# power_control.net
KiCad netlist of a schematic drawn in EAGLE
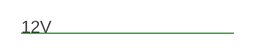
[diagram p0: schematic, sheet 1]
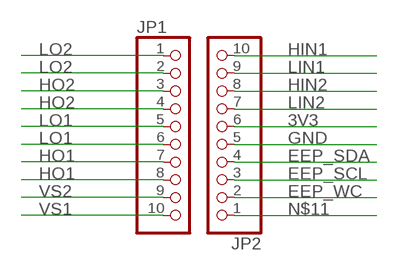
[diagram p1: schematic, sheet 2]
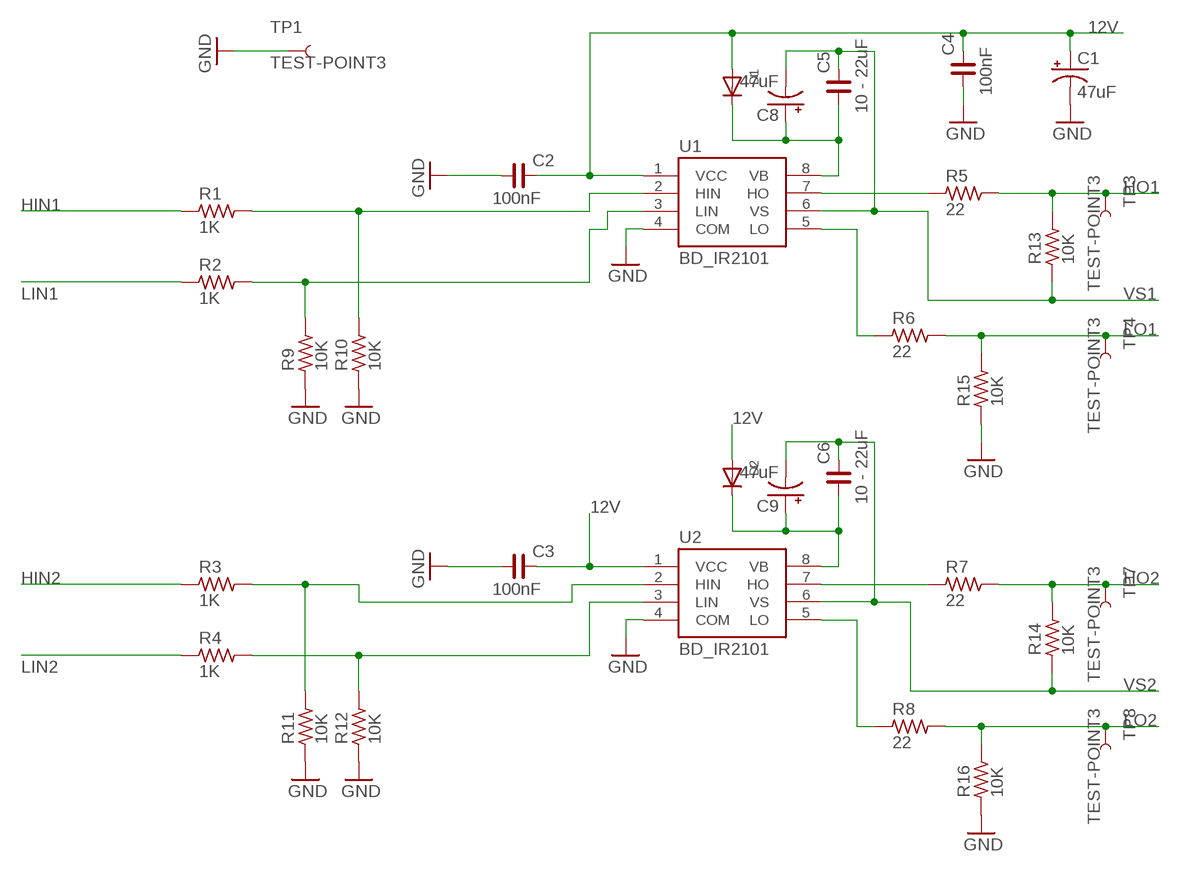
[diagram p2: schematic, sheet 3]
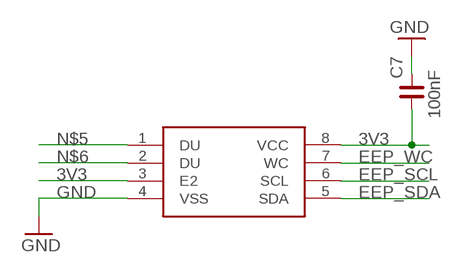
[diagram p3: schematic, sheet 4]

(export (version "E")
  (design (tool "Eeschema 10.0.6"))
  (components
    (comp (ref "JP1")
      (value "PINHD-1X10_2.54-SMD")
      (footprint "eagle-import:1X10SMD")
      (libsource (lib "eagle-import") (part "PINHD-1X10_2.54-SMD"))
    )
    (comp (ref "JP2")
      (value "PINHD-1X10_2.54-SMD")
      (footprint "eagle-import:1X10SMD")
      (libsource (lib "eagle-import") (part "PINHD-1X10_2.54-SMD"))
    )
    (comp (ref "C1")
      (value "47uF")
      (footprint "eagle-import:B_3528-21W")
      (libsource (lib "eagle-import") (part "CPOL-USB/3528-21W"))
    )
    (comp (ref "C2")
      (value "100nF")
      (footprint "eagle-import:C0201")
      (libsource (lib "eagle-import") (part "C_0201"))
    )
    (comp (ref "C3")
      (value "100nF")
      (footprint "eagle-import:C0201")
      (libsource (lib "eagle-import") (part "C_0201"))
    )
    (comp (ref "C4")
      (value "100nF")
      (footprint "eagle-import:C0201")
      (libsource (lib "eagle-import") (part "C_0201"))
    )
    (comp (ref "C5")
      (value "10 - 22uF")
      (footprint "eagle-import:C0805")
      (libsource (lib "eagle-import") (part "C_0805"))
    )
    (comp (ref "C6")
      (value "10 - 22uF")
      (footprint "eagle-import:C0805")
      (libsource (lib "eagle-import") (part "C_0805"))
    )
    (comp (ref "C8")
      (value "47uF")
      (footprint "eagle-import:B_3528-21W")
      (libsource (lib "eagle-import") (part "CPOL-USB/3528-21W"))
    )
    (comp (ref "C9")
      (value "47uF")
      (footprint "eagle-import:B_3528-21W")
      (libsource (lib "eagle-import") (part "CPOL-USB/3528-21W"))
    )
    (comp (ref "D1")
      (value "DIODESOD-523")
      (footprint "eagle-import:SOD-523")
      (libsource (lib "eagle-import") (part "DIODESOD-523"))
    )
    (comp (ref "D2")
      (value "DIODESOD-523")
      (footprint "eagle-import:SOD-523")
      (libsource (lib "eagle-import") (part "DIODESOD-523"))
    )
    (comp (ref "R1")
      (value "1K")
      (footprint "eagle-import:R0201")
      (libsource (lib "eagle-import") (part "R_0201"))
    )
    (comp (ref "R2")
      (value "1K")
      (footprint "eagle-import:R0201")
      (libsource (lib "eagle-import") (part "R_0201"))
    )
    (comp (ref "R3")
      (value "1K")
      (footprint "eagle-import:R0201")
      (libsource (lib "eagle-import") (part "R_0201"))
    )
    (comp (ref "R4")
      (value "1K")
      (footprint "eagle-import:R0201")
      (libsource (lib "eagle-import") (part "R_0201"))
    )
    (comp (ref "R5")
      (value "22")
      (footprint "eagle-import:R0805")
      (libsource (lib "eagle-import") (part "R_0805"))
    )
    (comp (ref "R6")
      (value "22")
      (footprint "eagle-import:R0805")
      (libsource (lib "eagle-import") (part "R_0805"))
    )
    (comp (ref "R7")
      (value "22")
      (footprint "eagle-import:R0805")
      (libsource (lib "eagle-import") (part "R_0805"))
    )
    (comp (ref "R8")
      (value "22")
      (footprint "eagle-import:R0805")
      (libsource (lib "eagle-import") (part "R_0805"))
    )
    (comp (ref "R9")
      (value "10K")
      (footprint "eagle-import:R0201")
      (libsource (lib "eagle-import") (part "R_0201"))
    )
    (comp (ref "R10")
      (value "10K")
      (footprint "eagle-import:R0201")
      (libsource (lib "eagle-import") (part "R_0201"))
    )
    (comp (ref "R11")
      (value "10K")
      (footprint "eagle-import:R0201")
      (libsource (lib "eagle-import") (part "R_0201"))
    )
    (comp (ref "R12")
      (value "10K")
      (footprint "eagle-import:R0201")
      (libsource (lib "eagle-import") (part "R_0201"))
    )
    (comp (ref "R13")
      (value "10K")
      (footprint "eagle-import:R0805")
      (libsource (lib "eagle-import") (part "R_0805"))
    )
    (comp (ref "R14")
      (value "10K")
      (footprint "eagle-import:R0805")
      (libsource (lib "eagle-import") (part "R_0805"))
    )
    (comp (ref "R15")
      (value "10K")
      (footprint "eagle-import:R0805")
      (libsource (lib "eagle-import") (part "R_0805"))
    )
    (comp (ref "R16")
      (value "10K")
      (footprint "eagle-import:R0805")
      (libsource (lib "eagle-import") (part "R_0805"))
    )
    (comp (ref "TP1")
      (value "TEST-POINT3")
      (footprint "eagle-import:PAD.03X.03")
      (libsource (lib "eagle-import") (part "TEST-POINT3"))
    )
    (comp (ref "TP3")
      (value "TEST-POINT3")
      (footprint "eagle-import:PAD.03X.03")
      (libsource (lib "eagle-import") (part "TEST-POINT3"))
    )
    (comp (ref "TP4")
      (value "TEST-POINT3")
      (footprint "eagle-import:PAD.03X.03")
      (libsource (lib "eagle-import") (part "TEST-POINT3"))
    )
    (comp (ref "TP7")
      (value "TEST-POINT3")
      (footprint "eagle-import:PAD.03X.03")
      (libsource (lib "eagle-import") (part "TEST-POINT3"))
    )
    (comp (ref "TP8")
      (value "TEST-POINT3")
      (footprint "eagle-import:PAD.03X.03")
      (libsource (lib "eagle-import") (part "TEST-POINT3"))
    )
    (comp (ref "U1")
      (value "BD_IR2101")
      (footprint "eagle-import:SO8")
      (libsource (lib "eagle-import") (part "BD_IR2101"))
    )
    (comp (ref "U2")
      (value "BD_IR2101")
      (footprint "eagle-import:SO8")
      (libsource (lib "eagle-import") (part "BD_IR2101"))
    )
    (comp (ref "C7")
      (value "100nF")
      (footprint "eagle-import:C0201")
      (libsource (lib "eagle-import") (part "C_0201"))
    )
    (comp (ref "M24M02")
      (value "M24M02-DRMN6TP")
      (footprint "eagle-import:SO08")
      (libsource (lib "eagle-import") (part "M24M02-DRMN6TP"))
    )
  )
  (nets
    (net (code "1") (name "3V3") (class "Default")
      (node (ref "C7") (pin "1") (pinfunction "1_1") (pintype "passive"))
      (node (ref "JP2") (pin "6") (pinfunction "6_6") (pintype "passive"))
      (node (ref "M24M02") (pin "3") (pinfunction "E2_3") (pintype "bidirectional"))
      (node (ref "M24M02") (pin "8") (pinfunction "VCC_8") (pintype "bidirectional"))
    )
    (net (code "2") (name "12V") (class "Default")
      (node (ref "C1") (pin "+") (pinfunction "+_+") (pintype "passive"))
      (node (ref "C2") (pin "2") (pinfunction "2_2") (pintype "passive"))
      (node (ref "C3") (pin "2") (pinfunction "2_2") (pintype "passive"))
      (node (ref "C4") (pin "2") (pinfunction "2_2") (pintype "passive"))
      (node (ref "D1") (pin "A") (pinfunction "A_A") (pintype "passive"))
      (node (ref "D2") (pin "A") (pinfunction "A_A") (pintype "passive"))
      (node (ref "U1") (pin "1") (pinfunction "VCC_1") (pintype "bidirectional"))
      (node (ref "U2") (pin "1") (pinfunction "VCC_1") (pintype "bidirectional"))
    )
    (net (code "3") (name "EEP_SCL") (class "Default")
      (node (ref "JP2") (pin "3") (pinfunction "3_3") (pintype "passive"))
      (node (ref "M24M02") (pin "6") (pinfunction "SCL_6") (pintype "bidirectional"))
    )
    (net (code "4") (name "EEP_SDA") (class "Default")
      (node (ref "JP2") (pin "4") (pinfunction "4_4") (pintype "passive"))
      (node (ref "M24M02") (pin "5") (pinfunction "SDA_5") (pintype "bidirectional"))
    )
    (net (code "5") (name "EEP_WC") (class "Default")
      (node (ref "JP2") (pin "2") (pinfunction "2_2") (pintype "passive"))
      (node (ref "M24M02") (pin "7") (pinfunction "WC_7") (pintype "bidirectional"))
    )
    (net (code "6") (name "GND") (class "Default")
      (node (ref "C1") (pin "-") (pinfunction "-_-") (pintype "passive"))
      (node (ref "C2") (pin "1") (pinfunction "1_1") (pintype "passive"))
      (node (ref "C3") (pin "1") (pinfunction "1_1") (pintype "passive"))
      (node (ref "C4") (pin "1") (pinfunction "1_1") (pintype "passive"))
      (node (ref "C7") (pin "2") (pinfunction "2_2") (pintype "passive"))
      (node (ref "JP2") (pin "5") (pinfunction "5_5") (pintype "passive"))
      (node (ref "M24M02") (pin "4") (pinfunction "VSS_4") (pintype "bidirectional"))
      (node (ref "R10") (pin "1") (pinfunction "1_1") (pintype "passive"))
      (node (ref "R11") (pin "1") (pinfunction "1_1") (pintype "passive"))
      (node (ref "R12") (pin "1") (pinfunction "1_1") (pintype "passive"))
      (node (ref "R15") (pin "1") (pinfunction "1_1") (pintype "passive"))
      (node (ref "R16") (pin "1") (pinfunction "1_1") (pintype "passive"))
      (node (ref "R9") (pin "1") (pinfunction "1_1") (pintype "passive"))
      (node (ref "TP1") (pin "P$1") (pinfunction "1_P$1") (pintype "bidirectional"))
      (node (ref "U1") (pin "4") (pinfunction "COM_4") (pintype "bidirectional"))
      (node (ref "U2") (pin "4") (pinfunction "COM_4") (pintype "bidirectional"))
    )
    (net (code "7") (name "HIN1") (class "Default")
      (node (ref "JP2") (pin "10") (pinfunction "10_10") (pintype "passive"))
      (node (ref "R1") (pin "1") (pinfunction "1_1") (pintype "passive"))
    )
    (net (code "8") (name "HIN2") (class "Default")
      (node (ref "JP2") (pin "8") (pinfunction "8_8") (pintype "passive"))
      (node (ref "R3") (pin "1") (pinfunction "1_1") (pintype "passive"))
    )
    (net (code "9") (name "HO1") (class "Default")
      (node (ref "JP1") (pin "7") (pinfunction "7_7") (pintype "passive"))
      (node (ref "JP1") (pin "8") (pinfunction "8_8") (pintype "passive"))
      (node (ref "R13") (pin "2") (pinfunction "2_2") (pintype "passive"))
      (node (ref "R5") (pin "2") (pinfunction "2_2") (pintype "passive"))
      (node (ref "TP3") (pin "P$1") (pinfunction "1_P$1") (pintype "bidirectional"))
    )
    (net (code "10") (name "HO2") (class "Default")
      (node (ref "JP1") (pin "3") (pinfunction "3_3") (pintype "passive"))
      (node (ref "JP1") (pin "4") (pinfunction "4_4") (pintype "passive"))
      (node (ref "R14") (pin "2") (pinfunction "2_2") (pintype "passive"))
      (node (ref "R7") (pin "2") (pinfunction "2_2") (pintype "passive"))
      (node (ref "TP7") (pin "P$1") (pinfunction "1_P$1") (pintype "bidirectional"))
    )
    (net (code "11") (name "LIN1") (class "Default")
      (node (ref "JP2") (pin "9") (pinfunction "9_9") (pintype "passive"))
      (node (ref "R2") (pin "1") (pinfunction "1_1") (pintype "passive"))
    )
    (net (code "12") (name "LIN2") (class "Default")
      (node (ref "JP2") (pin "7") (pinfunction "7_7") (pintype "passive"))
      (node (ref "R4") (pin "1") (pinfunction "1_1") (pintype "passive"))
    )
    (net (code "13") (name "LO1") (class "Default")
      (node (ref "JP1") (pin "5") (pinfunction "5_5") (pintype "passive"))
      (node (ref "JP1") (pin "6") (pinfunction "6_6") (pintype "passive"))
      (node (ref "R15") (pin "2") (pinfunction "2_2") (pintype "passive"))
      (node (ref "R6") (pin "2") (pinfunction "2_2") (pintype "passive"))
      (node (ref "TP4") (pin "P$1") (pinfunction "1_P$1") (pintype "bidirectional"))
    )
    (net (code "14") (name "LO2") (class "Default")
      (node (ref "JP1") (pin "1") (pinfunction "1_1") (pintype "passive"))
      (node (ref "JP1") (pin "2") (pinfunction "2_2") (pintype "passive"))
      (node (ref "R16") (pin "2") (pinfunction "2_2") (pintype "passive"))
      (node (ref "R8") (pin "2") (pinfunction "2_2") (pintype "passive"))
      (node (ref "TP8") (pin "P$1") (pinfunction "1_P$1") (pintype "bidirectional"))
    )
    (net (code "15") (name "N$5") (class "Default")
      (node (ref "M24M02") (pin "1") (pinfunction "DU_1") (pintype "bidirectional"))
    )
    (net (code "16") (name "N$6") (class "Default")
      (node (ref "M24M02") (pin "2") (pinfunction "DU_2") (pintype "bidirectional"))
    )
    (net (code "17") (name "N$11") (class "Default")
      (node (ref "JP2") (pin "1") (pinfunction "1_1") (pintype "passive"))
    )
    (net (code "18") (name "Net-(D1-C)") (class "Default")
      (node (ref "C5") (pin "1") (pinfunction "1_1") (pintype "passive"))
      (node (ref "C8") (pin "+") (pinfunction "+_+") (pintype "passive"))
      (node (ref "D1") (pin "K") (pinfunction "C_K") (pintype "passive"))
      (node (ref "U1") (pin "8") (pinfunction "VB_8") (pintype "bidirectional"))
    )
    (net (code "19") (name "Net-(D2-C)") (class "Default")
      (node (ref "C6") (pin "1") (pinfunction "1_1") (pintype "passive"))
      (node (ref "C9") (pin "+") (pinfunction "+_+") (pintype "passive"))
      (node (ref "D2") (pin "K") (pinfunction "C_K") (pintype "passive"))
      (node (ref "U2") (pin "8") (pinfunction "VB_8") (pintype "bidirectional"))
    )
    (net (code "20") (name "Net-(U1-HIN)") (class "Default")
      (node (ref "R1") (pin "2") (pinfunction "2_2") (pintype "passive"))
      (node (ref "R10") (pin "2") (pinfunction "2_2") (pintype "passive"))
      (node (ref "U1") (pin "2") (pinfunction "HIN_2") (pintype "bidirectional"))
    )
    (net (code "21") (name "Net-(U1-HO)") (class "Default")
      (node (ref "R5") (pin "1") (pinfunction "1_1") (pintype "passive"))
      (node (ref "U1") (pin "7") (pinfunction "HO_7") (pintype "bidirectional"))
    )
    (net (code "22") (name "Net-(U1-LIN)") (class "Default")
      (node (ref "R2") (pin "2") (pinfunction "2_2") (pintype "passive"))
      (node (ref "R9") (pin "2") (pinfunction "2_2") (pintype "passive"))
      (node (ref "U1") (pin "3") (pinfunction "LIN_3") (pintype "bidirectional"))
    )
    (net (code "23") (name "Net-(U1-LO)") (class "Default")
      (node (ref "R6") (pin "1") (pinfunction "1_1") (pintype "passive"))
      (node (ref "U1") (pin "5") (pinfunction "LO_5") (pintype "bidirectional"))
    )
    (net (code "24") (name "Net-(U2-HIN)") (class "Default")
      (node (ref "R11") (pin "2") (pinfunction "2_2") (pintype "passive"))
      (node (ref "R3") (pin "2") (pinfunction "2_2") (pintype "passive"))
      (node (ref "U2") (pin "2") (pinfunction "HIN_2") (pintype "bidirectional"))
    )
    (net (code "25") (name "Net-(U2-HO)") (class "Default")
      (node (ref "R7") (pin "1") (pinfunction "1_1") (pintype "passive"))
      (node (ref "U2") (pin "7") (pinfunction "HO_7") (pintype "bidirectional"))
    )
    (net (code "26") (name "Net-(U2-LIN)") (class "Default")
      (node (ref "R12") (pin "2") (pinfunction "2_2") (pintype "passive"))
      (node (ref "R4") (pin "2") (pinfunction "2_2") (pintype "passive"))
      (node (ref "U2") (pin "3") (pinfunction "LIN_3") (pintype "bidirectional"))
    )
    (net (code "27") (name "Net-(U2-LO)") (class "Default")
      (node (ref "R8") (pin "1") (pinfunction "1_1") (pintype "passive"))
      (node (ref "U2") (pin "5") (pinfunction "LO_5") (pintype "bidirectional"))
    )
    (net (code "28") (name "VS1") (class "Default")
      (node (ref "C5") (pin "2") (pinfunction "2_2") (pintype "passive"))
      (node (ref "C8") (pin "-") (pinfunction "-_-") (pintype "passive"))
      (node (ref "JP1") (pin "10") (pinfunction "10_10") (pintype "passive"))
      (node (ref "R13") (pin "1") (pinfunction "1_1") (pintype "passive"))
      (node (ref "U1") (pin "6") (pinfunction "VS_6") (pintype "bidirectional"))
    )
    (net (code "29") (name "VS2") (class "Default")
      (node (ref "C6") (pin "2") (pinfunction "2_2") (pintype "passive"))
      (node (ref "C9") (pin "-") (pinfunction "-_-") (pintype "passive"))
      (node (ref "JP1") (pin "9") (pinfunction "9_9") (pintype "passive"))
      (node (ref "R14") (pin "1") (pinfunction "1_1") (pintype "passive"))
      (node (ref "U2") (pin "6") (pinfunction "VS_6") (pintype "bidirectional"))
    )
  )
)
